# IMX425LLJ_MEZ.net
KiCad netlist of a schematic drawn in Altium Designer
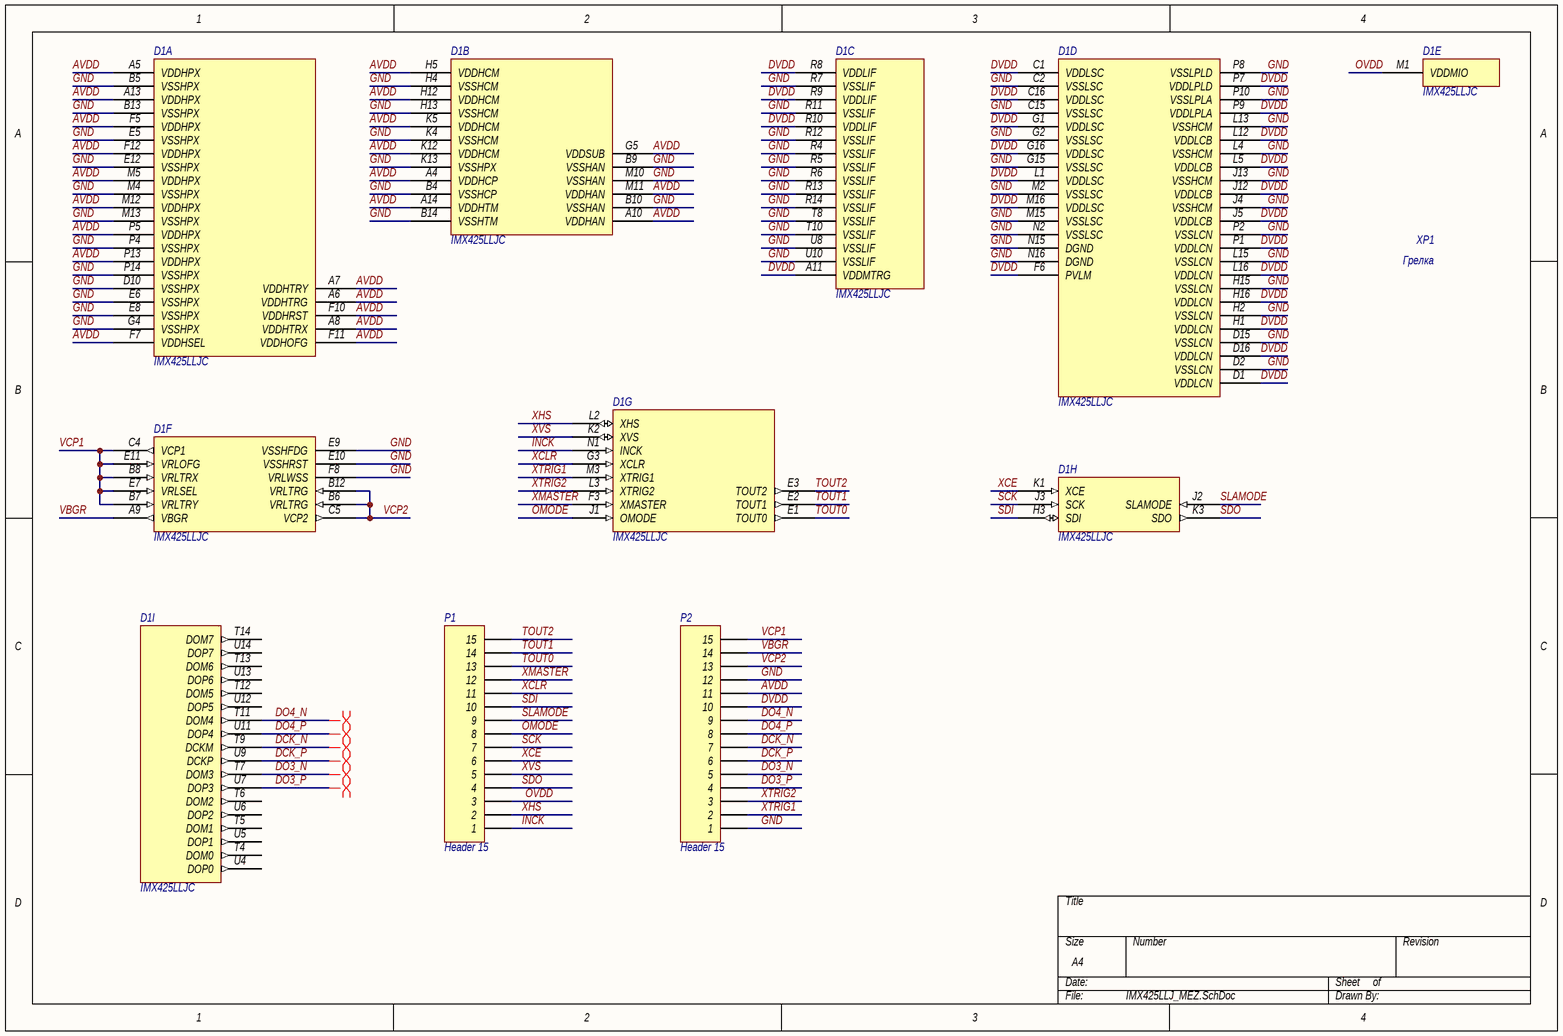
[diagram p0: IMX425LLJ_MEZ.SchDoc]

(export (version "E")
  (design (tool "Eeschema 10.0.6"))
  (components
    (comp (ref "D1")
      (value "IMX425LLJC")
      (footprint "IMX425LLJC")
      (libsource (lib "eic_lib") (part "IMX425LLJC"))
    )
    (comp (ref "P1")
      (value "Header 15")
      (footprint "HDR1X15")
      (description "Header, 15-Pin")
      (fields (field (name "PUBLISHER") "Altium Limited"))
      (libsource (lib "Miscellaneous Connectors") (part "Header 15"))
    )
    (comp (ref "P2")
      (value "Header 15")
      (footprint "HDR1X15")
      (description "Header, 15-Pin")
      (fields (field (name "PUBLISHER") "Altium Limited"))
      (libsource (lib "Miscellaneous Connectors") (part "Header 15"))
    )
    (comp (ref "XP1") (value "Грелка") (footprint "Грелка") (libsource (lib "VPL") (part "Грелка")))
  )
  (nets
    (net (code "1") (name "/AVDD") (class "Default")
      (node (ref "D1") (pin "A10") (pinfunction "VDDHAN_A10") (pintype "power_in"))
      (node (ref "D1") (pin "A13") (pinfunction "VDDHPX_A13") (pintype "power_in"))
      (node (ref "D1") (pin "A14") (pinfunction "VDDHTM_A14") (pintype "power_in"))
      (node (ref "D1") (pin "A4") (pinfunction "VDDHCP_A4") (pintype "power_in"))
      (node (ref "D1") (pin "A5") (pinfunction "VDDHPX_A5") (pintype "power_in"))
      (node (ref "D1") (pin "A6") (pinfunction "VDDHTRG_A6") (pintype "power_in"))
      (node (ref "D1") (pin "A7") (pinfunction "VDDHTRY_A7") (pintype "power_in"))
      (node (ref "D1") (pin "A8") (pinfunction "VDDHTRX_A8") (pintype "power_in"))
      (node (ref "D1") (pin "F10") (pinfunction "VDDHRST_F10") (pintype "power_in"))
      (node (ref "D1") (pin "F11") (pinfunction "VDDHOFG_F11") (pintype "power_in"))
      (node (ref "D1") (pin "F12") (pinfunction "VDDHPX_F12") (pintype "power_in"))
      (node (ref "D1") (pin "F5") (pinfunction "VDDHPX_F5") (pintype "power_in"))
      (node (ref "D1") (pin "F7") (pinfunction "VDDHSEL_F7") (pintype "power_in"))
      (node (ref "D1") (pin "G5") (pinfunction "VDDSUB_G5") (pintype "power_in"))
      (node (ref "D1") (pin "H12") (pinfunction "VDDHCM_H12") (pintype "power_in"))
      (node (ref "D1") (pin "H5") (pinfunction "VDDHCM_H5") (pintype "power_in"))
      (node (ref "D1") (pin "K12") (pinfunction "VDDHCM_K12") (pintype "power_in"))
      (node (ref "D1") (pin "K5") (pinfunction "VDDHCM_K5") (pintype "power_in"))
      (node (ref "D1") (pin "M11") (pinfunction "VDDHAN_M11") (pintype "power_in"))
      (node (ref "D1") (pin "M12") (pinfunction "VDDHPX_M12") (pintype "power_in"))
      (node (ref "D1") (pin "M5") (pinfunction "VDDHPX_M5") (pintype "power_in"))
      (node (ref "D1") (pin "P13") (pinfunction "VDDHPX_P13") (pintype "power_in"))
      (node (ref "D1") (pin "P5") (pinfunction "VDDHPX_P5") (pintype "power_in"))
      (node (ref "P2") (pin "11") (pinfunction "11_11") (pintype "passive"))
    )
    (net (code "2") (name "/DCK_N") (class "Default")
      (node (ref "D1") (pin "T9") (pinfunction "DCKM_T9") (pintype "output"))
      (node (ref "P2") (pin "7") (pinfunction "7_7") (pintype "passive"))
    )
    (net (code "3") (name "/DCK_P") (class "Default")
      (node (ref "D1") (pin "U9") (pinfunction "DCKP_U9") (pintype "output"))
      (node (ref "P2") (pin "6") (pinfunction "6_6") (pintype "passive"))
    )
    (net (code "4") (name "/DO3_N") (class "Default")
      (node (ref "D1") (pin "T7") (pinfunction "DOM3_T7") (pintype "output"))
      (node (ref "P2") (pin "5") (pinfunction "5_5") (pintype "passive"))
    )
    (net (code "5") (name "/DO3_P") (class "Default")
      (node (ref "D1") (pin "U7") (pinfunction "DOP3_U7") (pintype "output"))
      (node (ref "P2") (pin "4") (pinfunction "4_4") (pintype "passive"))
    )
    (net (code "6") (name "/DO4_N") (class "Default")
      (node (ref "D1") (pin "T11") (pinfunction "DOM4_T11") (pintype "output"))
      (node (ref "P2") (pin "9") (pinfunction "9_9") (pintype "passive"))
    )
    (net (code "7") (name "/DO4_P") (class "Default")
      (node (ref "D1") (pin "U11") (pinfunction "DOP4_U11") (pintype "output"))
      (node (ref "P2") (pin "8") (pinfunction "8_8") (pintype "passive"))
    )
    (net (code "8") (name "/DVDD") (class "Default")
      (node (ref "D1") (pin "A11") (pinfunction "VDDMTRG_A11") (pintype "power_in"))
      (node (ref "D1") (pin "C1") (pinfunction "VDDLSC_C1") (pintype "power_in"))
      (node (ref "D1") (pin "C16") (pinfunction "VDDLSC_C16") (pintype "power_in"))
      (node (ref "D1") (pin "D1") (pinfunction "VDDLCN_D1") (pintype "power_in"))
      (node (ref "D1") (pin "D16") (pinfunction "VDDLCN_D16") (pintype "power_in"))
      (node (ref "D1") (pin "F6") (pinfunction "PVLM_F6") (pintype "power_in"))
      (node (ref "D1") (pin "G1") (pinfunction "VDDLSC_G1") (pintype "power_in"))
      (node (ref "D1") (pin "G16") (pinfunction "VDDLSC_G16") (pintype "power_in"))
      (node (ref "D1") (pin "H1") (pinfunction "VDDLCN_H1") (pintype "power_in"))
      (node (ref "D1") (pin "H16") (pinfunction "VDDLCN_H16") (pintype "power_in"))
      (node (ref "D1") (pin "J12") (pinfunction "VDDLCB_J12") (pintype "power_in"))
      (node (ref "D1") (pin "J5") (pinfunction "VDDLCB_J5") (pintype "power_in"))
      (node (ref "D1") (pin "L1") (pinfunction "VDDLSC_L1") (pintype "power_in"))
      (node (ref "D1") (pin "L12") (pinfunction "VDDLCB_L12") (pintype "power_in"))
      (node (ref "D1") (pin "L16") (pinfunction "VDDLCN_L16") (pintype "power_in"))
      (node (ref "D1") (pin "L5") (pinfunction "VDDLCB_L5") (pintype "power_in"))
      (node (ref "D1") (pin "M16") (pinfunction "VDDLSC_M16") (pintype "power_in"))
      (node (ref "D1") (pin "P1") (pinfunction "VDDLCN_P1") (pintype "power_in"))
      (node (ref "D1") (pin "P7") (pinfunction "VDDLPLD_P7") (pintype "power_in"))
      (node (ref "D1") (pin "P9") (pinfunction "VDDLPLA_P9") (pintype "power_in"))
      (node (ref "D1") (pin "R10") (pinfunction "VDDLIF_R10") (pintype "power_in"))
      (node (ref "D1") (pin "R8") (pinfunction "VDDLIF_R8") (pintype "power_in"))
      (node (ref "D1") (pin "R9") (pinfunction "VDDLIF_R9") (pintype "power_in"))
      (node (ref "P2") (pin "10") (pinfunction "10_10") (pintype "passive"))
    )
    (net (code "9") (name "/GND") (class "Default")
      (node (ref "D1") (pin "B10") (pinfunction "VSSHAN_B10") (pintype "power_in"))
      (node (ref "D1") (pin "B13") (pinfunction "VSSHPX_B13") (pintype "power_in"))
      (node (ref "D1") (pin "B14") (pinfunction "VSSHTM_B14") (pintype "power_in"))
      (node (ref "D1") (pin "B4") (pinfunction "VSSHCP_B4") (pintype "power_in"))
      (node (ref "D1") (pin "B5") (pinfunction "VSSHPX_B5") (pintype "power_in"))
      (node (ref "D1") (pin "B9") (pinfunction "VSSHAN_B9") (pintype "power_in"))
      (node (ref "D1") (pin "C15") (pinfunction "VSSLSC_C15") (pintype "power_in"))
      (node (ref "D1") (pin "C2") (pinfunction "VSSLSC_C2") (pintype "power_in"))
      (node (ref "D1") (pin "D10") (pinfunction "VSSHPX_D10") (pintype "power_in"))
      (node (ref "D1") (pin "D15") (pinfunction "VSSLCN_D15") (pintype "power_in"))
      (node (ref "D1") (pin "D2") (pinfunction "VSSLCN_D2") (pintype "power_in"))
      (node (ref "D1") (pin "E10") (pinfunction "VSSHRST_E10") (pintype "power_in"))
      (node (ref "D1") (pin "E12") (pinfunction "VSSHPX_E12") (pintype "power_in"))
      (node (ref "D1") (pin "E5") (pinfunction "VSSHPX_E5") (pintype "power_in"))
      (node (ref "D1") (pin "E6") (pinfunction "VSSHPX_E6") (pintype "power_in"))
      (node (ref "D1") (pin "E8") (pinfunction "VSSHPX_E8") (pintype "power_in"))
      (node (ref "D1") (pin "E9") (pinfunction "VSSHFDG_E9") (pintype "power_in"))
      (node (ref "D1") (pin "F8") (pinfunction "VRLWSS_F8") (pintype "power_in"))
      (node (ref "D1") (pin "G15") (pinfunction "VSSLSC_G15") (pintype "power_in"))
      (node (ref "D1") (pin "G2") (pinfunction "VSSLSC_G2") (pintype "power_in"))
      (node (ref "D1") (pin "G4") (pinfunction "VSSHPX_G4") (pintype "power_in"))
      (node (ref "D1") (pin "H13") (pinfunction "VSSHCM_H13") (pintype "power_in"))
      (node (ref "D1") (pin "H15") (pinfunction "VSSLCN_H15") (pintype "power_in"))
      (node (ref "D1") (pin "H2") (pinfunction "VSSLCN_H2") (pintype "power_in"))
      (node (ref "D1") (pin "H4") (pinfunction "VSSHCM_H4") (pintype "power_in"))
      (node (ref "D1") (pin "J13") (pinfunction "VSSHCM_J13") (pintype "power_in"))
      (node (ref "D1") (pin "J4") (pinfunction "VSSHCM_J4") (pintype "power_in"))
      (node (ref "D1") (pin "K13") (pinfunction "VSSHPX_K13") (pintype "power_in"))
      (node (ref "D1") (pin "K4") (pinfunction "VSSHCM_K4") (pintype "power_in"))
      (node (ref "D1") (pin "L13") (pinfunction "VSSHCM_L13") (pintype "power_in"))
      (node (ref "D1") (pin "L15") (pinfunction "VSSLCN_L15") (pintype "power_in"))
      (node (ref "D1") (pin "L4") (pinfunction "VSSHCM_L4") (pintype "power_in"))
      (node (ref "D1") (pin "M10") (pinfunction "VSSHAN_M10") (pintype "power_in"))
      (node (ref "D1") (pin "M13") (pinfunction "VSSHPX_M13") (pintype "power_in"))
      (node (ref "D1") (pin "M15") (pinfunction "VSSLSC_M15") (pintype "power_in"))
      (node (ref "D1") (pin "M2") (pinfunction "VSSLSC_M2") (pintype "power_in"))
      (node (ref "D1") (pin "M4") (pinfunction "VSSHPX_M4") (pintype "power_in"))
      (node (ref "D1") (pin "N15") (pinfunction "DGND_N15") (pintype "power_in"))
      (node (ref "D1") (pin "N16") (pinfunction "DGND_N16") (pintype "power_in"))
      (node (ref "D1") (pin "N2") (pinfunction "VSSLSC_N2") (pintype "power_in"))
      (node (ref "D1") (pin "P10") (pinfunction "VSSLPLA_P10") (pintype "power_in"))
      (node (ref "D1") (pin "P14") (pinfunction "VSSHPX_P14") (pintype "power_in"))
      (node (ref "D1") (pin "P2") (pinfunction "VSSLCN_P2") (pintype "power_in"))
      (node (ref "D1") (pin "P4") (pinfunction "VSSHPX_P4") (pintype "power_in"))
      (node (ref "D1") (pin "P8") (pinfunction "VSSLPLD_P8") (pintype "power_in"))
      (node (ref "D1") (pin "R11") (pinfunction "VSSLIF_R11") (pintype "power_in"))
      (node (ref "D1") (pin "R12") (pinfunction "VSSLIF_R12") (pintype "power_in"))
      (node (ref "D1") (pin "R13") (pinfunction "VSSLIF_R13") (pintype "power_in"))
      (node (ref "D1") (pin "R14") (pinfunction "VSSLIF_R14") (pintype "power_in"))
      (node (ref "D1") (pin "R4") (pinfunction "VSSLIF_R4") (pintype "power_in"))
      (node (ref "D1") (pin "R5") (pinfunction "VSSLIF_R5") (pintype "power_in"))
      (node (ref "D1") (pin "R6") (pinfunction "VSSLIF_R6") (pintype "power_in"))
      (node (ref "D1") (pin "R7") (pinfunction "VSSLIF_R7") (pintype "power_in"))
      (node (ref "D1") (pin "T10") (pinfunction "VSSLIF_T10") (pintype "power_in"))
      (node (ref "D1") (pin "T8") (pinfunction "VSSLIF_T8") (pintype "power_in"))
      (node (ref "D1") (pin "U10") (pinfunction "VSSLIF_U10") (pintype "power_in"))
      (node (ref "D1") (pin "U8") (pinfunction "VSSLIF_U8") (pintype "power_in"))
      (node (ref "P2") (pin "1") (pinfunction "1_1") (pintype "passive"))
      (node (ref "P2") (pin "12") (pinfunction "12_12") (pintype "passive"))
    )
    (net (code "10") (name "/INCK") (class "Default")
      (node (ref "D1") (pin "N1") (pinfunction "INCK_N1") (pintype "input"))
      (node (ref "P1") (pin "1") (pinfunction "1_1") (pintype "passive"))
    )
    (net (code "11") (name "/OMODE") (class "Default")
      (node (ref "D1") (pin "J1") (pinfunction "OMODE_J1") (pintype "input"))
      (node (ref "P1") (pin "8") (pinfunction "8_8") (pintype "passive"))
    )
    (net (code "12") (name "/OVDD") (class "Default")
      (node (ref "D1") (pin "M1") (pinfunction "VDDMIO_M1") (pintype "power_in"))
      (node (ref "P1") (pin "3") (pinfunction "3_3") (pintype "passive"))
    )
    (net (code "13") (name "/SCK") (class "Default")
      (node (ref "D1") (pin "J3") (pinfunction "SCK_J3") (pintype "input"))
      (node (ref "P1") (pin "7") (pinfunction "7_7") (pintype "passive"))
    )
    (net (code "14") (name "/SDI") (class "Default")
      (node (ref "D1") (pin "H3") (pinfunction "SDI_H3") (pintype "bidirectional"))
      (node (ref "P1") (pin "10") (pinfunction "10_10") (pintype "passive"))
    )
    (net (code "15") (name "/SDO") (class "Default")
      (node (ref "D1") (pin "K3") (pinfunction "SDO_K3") (pintype "output"))
      (node (ref "P1") (pin "4") (pinfunction "4_4") (pintype "passive"))
    )
    (net (code "16") (name "/SLAMODE") (class "Default")
      (node (ref "D1") (pin "J2") (pinfunction "SLAMODE_J2") (pintype "input"))
      (node (ref "P1") (pin "9") (pinfunction "9_9") (pintype "passive"))
    )
    (net (code "17") (name "/TOUT0") (class "Default")
      (node (ref "D1") (pin "E1") (pinfunction "TOUT0_E1") (pintype "output"))
      (node (ref "P1") (pin "13") (pinfunction "13_13") (pintype "passive"))
    )
    (net (code "18") (name "/TOUT1") (class "Default")
      (node (ref "D1") (pin "E2") (pinfunction "TOUT1_E2") (pintype "output"))
      (node (ref "P1") (pin "14") (pinfunction "14_14") (pintype "passive"))
    )
    (net (code "19") (name "/TOUT2") (class "Default")
      (node (ref "D1") (pin "E3") (pinfunction "TOUT2_E3") (pintype "output"))
      (node (ref "P1") (pin "15") (pinfunction "15_15") (pintype "passive"))
    )
    (net (code "20") (name "/VBGR") (class "Default")
      (node (ref "D1") (pin "A9") (pinfunction "VBGR_A9") (pintype "output"))
      (node (ref "P2") (pin "14") (pinfunction "14_14") (pintype "passive"))
    )
    (net (code "21") (name "/VCP1") (class "Default")
      (node (ref "D1") (pin "B7") (pinfunction "VRLTRY_B7") (pintype "input"))
      (node (ref "D1") (pin "B8") (pinfunction "VRLTRX_B8") (pintype "input"))
      (node (ref "D1") (pin "C4") (pinfunction "VCP1_C4") (pintype "output"))
      (node (ref "D1") (pin "E11") (pinfunction "VRLOFG_E11") (pintype "input"))
      (node (ref "D1") (pin "E7") (pinfunction "VRLSEL_E7") (pintype "input"))
      (node (ref "P2") (pin "15") (pinfunction "15_15") (pintype "passive"))
    )
    (net (code "22") (name "/VCP2") (class "Default")
      (node (ref "D1") (pin "B12") (pinfunction "VRLTRG_B12") (pintype "input"))
      (node (ref "D1") (pin "B6") (pinfunction "VRLTRG_B6") (pintype "input"))
      (node (ref "D1") (pin "C5") (pinfunction "VCP2_C5") (pintype "output"))
      (node (ref "P2") (pin "13") (pinfunction "13_13") (pintype "passive"))
    )
    (net (code "23") (name "/XCE") (class "Default")
      (node (ref "D1") (pin "K1") (pinfunction "XCE_K1") (pintype "input"))
      (node (ref "P1") (pin "6") (pinfunction "6_6") (pintype "passive"))
    )
    (net (code "24") (name "/XCLR") (class "Default")
      (node (ref "D1") (pin "G3") (pinfunction "XCLR_G3") (pintype "input"))
      (node (ref "P1") (pin "11") (pinfunction "11_11") (pintype "passive"))
    )
    (net (code "25") (name "/XHS") (class "Default")
      (node (ref "D1") (pin "L2") (pinfunction "XHS_L2") (pintype "bidirectional"))
      (node (ref "P1") (pin "2") (pinfunction "2_2") (pintype "passive"))
    )
    (net (code "26") (name "/XMASTER") (class "Default")
      (node (ref "D1") (pin "F3") (pinfunction "XMASTER_F3") (pintype "input"))
      (node (ref "P1") (pin "12") (pinfunction "12_12") (pintype "passive"))
    )
    (net (code "27") (name "/XTRIG1") (class "Default")
      (node (ref "D1") (pin "M3") (pinfunction "XTRIG1_M3") (pintype "input"))
      (node (ref "P2") (pin "2") (pinfunction "2_2") (pintype "passive"))
    )
    (net (code "28") (name "/XTRIG2") (class "Default")
      (node (ref "D1") (pin "L3") (pinfunction "XTRIG2_L3") (pintype "input"))
      (node (ref "P2") (pin "3") (pinfunction "3_3") (pintype "passive"))
    )
    (net (code "29") (name "/XVS") (class "Default")
      (node (ref "D1") (pin "K2") (pinfunction "XVS_K2") (pintype "bidirectional"))
      (node (ref "P1") (pin "5") (pinfunction "5_5") (pintype "passive"))
    )
    (net (code "30") (name "unconnected-(D1I-DOM0-PadT4)") (class "Default")
      (node (ref "D1") (pin "T4") (pinfunction "DOM0_T4") (pintype "output"))
    )
    (net (code "31") (name "unconnected-(D1I-DOM1-PadT5)") (class "Default")
      (node (ref "D1") (pin "T5") (pinfunction "DOM1_T5") (pintype "output"))
    )
    (net (code "32") (name "unconnected-(D1I-DOM2-PadT6)") (class "Default")
      (node (ref "D1") (pin "T6") (pinfunction "DOM2_T6") (pintype "output"))
    )
    (net (code "33") (name "unconnected-(D1I-DOM5-PadT12)") (class "Default")
      (node (ref "D1") (pin "T12") (pinfunction "DOM5_T12") (pintype "output"))
    )
    (net (code "34") (name "unconnected-(D1I-DOM6-PadT13)") (class "Default")
      (node (ref "D1") (pin "T13") (pinfunction "DOM6_T13") (pintype "output"))
    )
    (net (code "35") (name "unconnected-(D1I-DOM7-PadT14)") (class "Default")
      (node (ref "D1") (pin "T14") (pinfunction "DOM7_T14") (pintype "output"))
    )
    (net (code "36") (name "unconnected-(D1I-DOP0-PadU4)") (class "Default")
      (node (ref "D1") (pin "U4") (pinfunction "DOP0_U4") (pintype "output"))
    )
    (net (code "37") (name "unconnected-(D1I-DOP1-PadU5)") (class "Default")
      (node (ref "D1") (pin "U5") (pinfunction "DOP1_U5") (pintype "output"))
    )
    (net (code "38") (name "unconnected-(D1I-DOP2-PadU6)") (class "Default")
      (node (ref "D1") (pin "U6") (pinfunction "DOP2_U6") (pintype "output"))
    )
    (net (code "39") (name "unconnected-(D1I-DOP5-PadU12)") (class "Default")
      (node (ref "D1") (pin "U12") (pinfunction "DOP5_U12") (pintype "output"))
    )
    (net (code "40") (name "unconnected-(D1I-DOP6-PadU13)") (class "Default")
      (node (ref "D1") (pin "U13") (pinfunction "DOP6_U13") (pintype "output"))
    )
    (net (code "41") (name "unconnected-(D1I-DOP7-PadU14)") (class "Default")
      (node (ref "D1") (pin "U14") (pinfunction "DOP7_U14") (pintype "output"))
    )
  )
)
